# PIC32MZ.net
KiCad netlist of a schematic drawn in Altium Designer
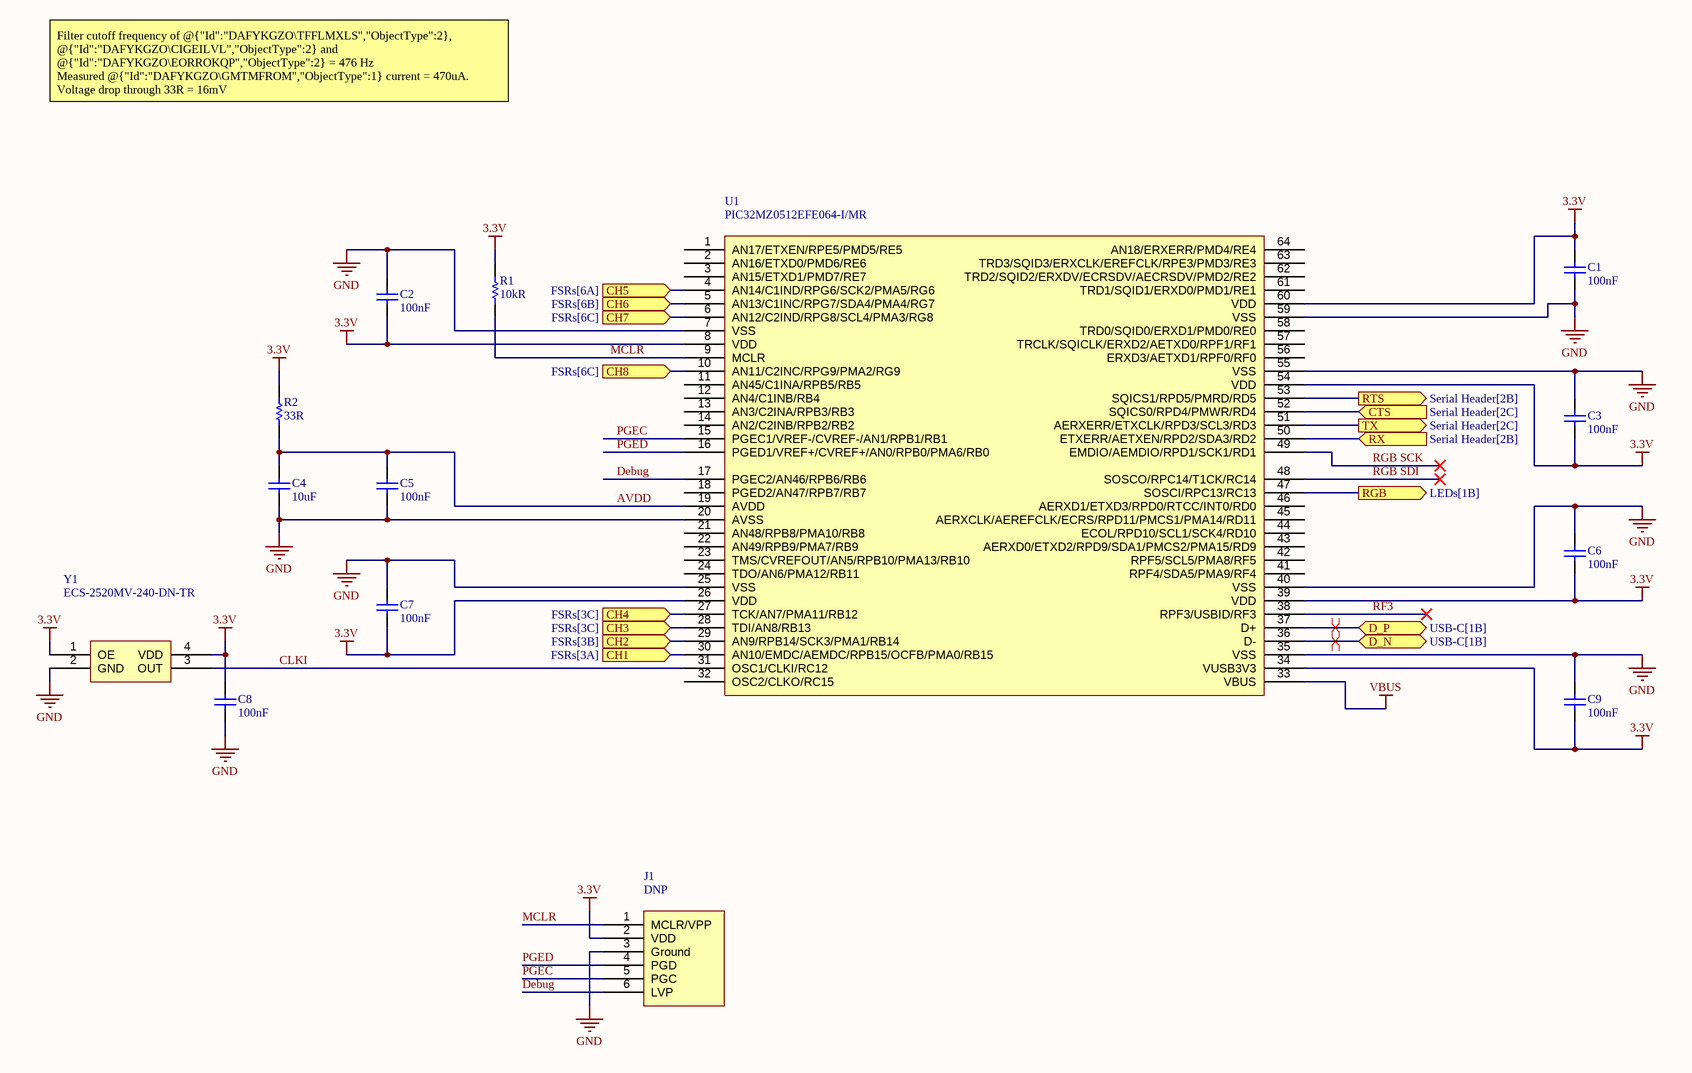
[diagram p0: PIC32MZ.SchDoc]

(export (version "E")
  (design (tool "Eeschema 10.0.6"))
  (components
    (comp (ref "C1") (value "100nF") (footprint "Capacitor 0402") (libsource (lib "x-io") (part "Capacitor")))
    (comp (ref "C2") (value "100nF") (footprint "Capacitor 0402") (libsource (lib "x-io") (part "Capacitor")))
    (comp (ref "C3") (value "100nF") (footprint "Capacitor 0402") (libsource (lib "x-io") (part "Capacitor")))
    (comp (ref "C4") (value "10uF") (footprint "Capacitor 0402") (libsource (lib "x-io") (part "Capacitor")))
    (comp (ref "C5") (value "100nF") (footprint "Capacitor 0402") (libsource (lib "x-io") (part "Capacitor")))
    (comp (ref "C6") (value "100nF") (footprint "Capacitor 0402") (libsource (lib "x-io") (part "Capacitor")))
    (comp (ref "C7") (value "100nF") (footprint "Capacitor 0402") (libsource (lib "x-io") (part "Capacitor")))
    (comp (ref "C8") (value "100nF") (footprint "Capacitor 0402") (libsource (lib "x-io") (part "Capacitor")))
    (comp (ref "C9") (value "100nF") (footprint "Capacitor 0402") (libsource (lib "x-io") (part "Capacitor")))
    (comp (ref "J1")
      (value "DNP")
      (footprint "Tag Connect No Legs")
      (libsource (lib "x-io") (part "MPLAB ICSP"))
    )
    (comp (ref "R1") (value "10kR") (footprint "Resistor 0402") (libsource (lib "x-io") (part "Resistor")))
    (comp (ref "R2") (value "33R") (footprint "Resistor 0402") (libsource (lib "x-io") (part "Resistor")))
    (comp (ref "U1")
      (value "PIC32MZ0512EFE064-I/MR")
      (footprint "QFN-64")
      (libsource (lib "x-io") (part "PIC32MZ2048EFH064"))
    )
    (comp (ref "Y1")
      (value "ECS-2520MV-240-DN-TR")
      (footprint "ECS 2x2.5mm")
      (libsource (lib "x-io") (part "Oscillator"))
    )
  )
  (nets
    (net (code "1") (name "/AVDD") (class "Default")
      (node (ref "C4") (pin "2") (pinfunction "2_2") (pintype "passive"))
      (node (ref "C5") (pin "2") (pinfunction "2_2") (pintype "passive"))
      (node (ref "R2") (pin "1") (pinfunction "1_1") (pintype "passive"))
      (node (ref "U1") (pin "19") (pinfunction "AVDD_19") (pintype "passive"))
    )
    (net (code "2") (name "/CH1") (class "Default")
      (node (ref "U1") (pin "30") (pinfunction "AN10/EMDC/AEMDC/RPB15/OCFB/PMA0/RB15_30") (pintype "passive"))
    )
    (net (code "3") (name "/CH2") (class "Default")
      (node (ref "U1") (pin "29") (pinfunction "AN9/RPB14/SCK3/PMA1/RB14_29") (pintype "passive"))
    )
    (net (code "4") (name "/CH3") (class "Default")
      (node (ref "U1") (pin "28") (pinfunction "TDI/AN8/RB13_28") (pintype "passive"))
    )
    (net (code "5") (name "/CH4") (class "Default")
      (node (ref "U1") (pin "27") (pinfunction "TCK/AN7/PMA11/RB12_27") (pintype "passive"))
    )
    (net (code "6") (name "/CH5") (class "Default")
      (node (ref "U1") (pin "4") (pinfunction "AN14/C1IND/RPG6/SCK2/PMA5/RG6_4") (pintype "passive"))
    )
    (net (code "7") (name "/CH6") (class "Default")
      (node (ref "U1") (pin "5") (pinfunction "AN13/C1INC/RPG7/SDA4/PMA4/RG7_5") (pintype "passive"))
    )
    (net (code "8") (name "/CH7") (class "Default")
      (node (ref "U1") (pin "6") (pinfunction "AN12/C2IND/RPG8/SCL4/PMA3/RG8_6") (pintype "passive"))
    )
    (net (code "9") (name "/CH8") (class "Default")
      (node (ref "U1") (pin "10") (pinfunction "AN11/C2INC/RPG9/PMA2/RG9_10") (pintype "passive"))
    )
    (net (code "10") (name "/CLKI") (class "Default")
      (node (ref "U1") (pin "31") (pinfunction "OSC1/CLKI/RC12_31") (pintype "passive"))
      (node (ref "Y1") (pin "3") (pinfunction "OUT_3") (pintype "passive"))
    )
    (net (code "11") (name "/CTS") (class "Default")
      (node (ref "U1") (pin "52") (pinfunction "SQICS0/RPD4/PMWR/RD4_52") (pintype "passive"))
    )
    (net (code "12") (name "/D_N") (class "Default")
      (node (ref "U1") (pin "36") (pinfunction "D-_36") (pintype "passive"))
    )
    (net (code "13") (name "/D_P") (class "Default")
      (node (ref "U1") (pin "37") (pinfunction "D+_37") (pintype "passive"))
    )
    (net (code "14") (name "/Debug") (class "Default")
      (node (ref "J1") (pin "6") (pinfunction "LVP_6") (pintype "passive"))
      (node (ref "U1") (pin "17") (pinfunction "PGEC2/AN46/RPB6/RB6_17") (pintype "passive"))
    )
    (net (code "15") (name "/MCLR") (class "Default")
      (node (ref "J1") (pin "1") (pinfunction "MCLR/VPP_1") (pintype "passive"))
      (node (ref "R1") (pin "1") (pinfunction "1_1") (pintype "passive"))
      (node (ref "U1") (pin "9") (pinfunction "MCLR_9") (pintype "passive"))
    )
    (net (code "16") (name "/PGEC") (class "Default")
      (node (ref "J1") (pin "5") (pinfunction "PGC_5") (pintype "passive"))
      (node (ref "U1") (pin "15") (pinfunction "PGEC1/VREF-/CVREF-/AN1/RPB1/RB1_15") (pintype "passive"))
    )
    (net (code "17") (name "/PGED") (class "Default")
      (node (ref "J1") (pin "4") (pinfunction "PGD_4") (pintype "passive"))
      (node (ref "U1") (pin "16") (pinfunction "PGED1/VREF+/CVREF+/AN0/RPB0/PMA6/RB0_16") (pintype "passive"))
    )
    (net (code "18") (name "/RF3") (class "Default")
      (node (ref "U1") (pin "38") (pinfunction "RPF3/USBID/RF3_38") (pintype "passive+no_connect"))
    )
    (net (code "19") (name "/RGB") (class "Default")
      (node (ref "U1") (pin "47") (pinfunction "SOSCI/RPC13/RC13_47") (pintype "passive"))
    )
    (net (code "20") (name "/RGB SCK") (class "Default")
      (node (ref "U1") (pin "49") (pinfunction "EMDIO/AEMDIO/RPD1/SCK1/RD1_49") (pintype "passive+no_connect"))
    )
    (net (code "21") (name "/RGB SDI") (class "Default")
      (node (ref "U1") (pin "48") (pinfunction "SOSCO/RPC14/T1CK/RC14_48") (pintype "passive+no_connect"))
    )
    (net (code "22") (name "/RTS") (class "Default")
      (node (ref "U1") (pin "53") (pinfunction "SQICS1/RPD5/PMRD/RD5_53") (pintype "passive"))
    )
    (net (code "23") (name "/RX") (class "Default")
      (node (ref "U1") (pin "50") (pinfunction "ETXERR/AETXEN/RPD2/SDA3/RD2_50") (pintype "passive"))
    )
    (net (code "24") (name "/TX") (class "Default")
      (node (ref "U1") (pin "51") (pinfunction "AERXERR/ETXCLK/RPD3/SCL3/RD3_51") (pintype "passive"))
    )
    (net (code "25") (name "3.3V") (class "Default")
      (node (ref "C1") (pin "2") (pinfunction "2_2") (pintype "passive"))
      (node (ref "C2") (pin "1") (pinfunction "1_1") (pintype "passive"))
      (node (ref "C3") (pin "1") (pinfunction "1_1") (pintype "passive"))
      (node (ref "C6") (pin "1") (pinfunction "1_1") (pintype "passive"))
      (node (ref "C7") (pin "1") (pinfunction "1_1") (pintype "passive"))
      (node (ref "C8") (pin "2") (pinfunction "2_2") (pintype "passive"))
      (node (ref "C9") (pin "1") (pinfunction "1_1") (pintype "passive"))
      (node (ref "J1") (pin "2") (pinfunction "VDD_2") (pintype "passive"))
      (node (ref "R1") (pin "2") (pinfunction "2_2") (pintype "passive"))
      (node (ref "R2") (pin "2") (pinfunction "2_2") (pintype "passive"))
      (node (ref "U1") (pin "26") (pinfunction "VDD_26") (pintype "passive"))
      (node (ref "U1") (pin "34") (pinfunction "VUSB3V3_34") (pintype "passive"))
      (node (ref "U1") (pin "39") (pinfunction "VDD_39") (pintype "passive"))
      (node (ref "U1") (pin "54") (pinfunction "VDD_54") (pintype "passive"))
      (node (ref "U1") (pin "60") (pinfunction "VDD_60") (pintype "passive"))
      (node (ref "U1") (pin "8") (pinfunction "VDD_8") (pintype "passive"))
      (node (ref "Y1") (pin "1") (pinfunction "OE_1") (pintype "passive"))
      (node (ref "Y1") (pin "4") (pinfunction "VDD_4") (pintype "passive"))
    )
    (net (code "26") (name "GND") (class "Default")
      (node (ref "C1") (pin "1") (pinfunction "1_1") (pintype "passive"))
      (node (ref "C2") (pin "2") (pinfunction "2_2") (pintype "passive"))
      (node (ref "C3") (pin "2") (pinfunction "2_2") (pintype "passive"))
      (node (ref "C4") (pin "1") (pinfunction "1_1") (pintype "passive"))
      (node (ref "C5") (pin "1") (pinfunction "1_1") (pintype "passive"))
      (node (ref "C6") (pin "2") (pinfunction "2_2") (pintype "passive"))
      (node (ref "C7") (pin "2") (pinfunction "2_2") (pintype "passive"))
      (node (ref "C8") (pin "1") (pinfunction "1_1") (pintype "passive"))
      (node (ref "C9") (pin "2") (pinfunction "2_2") (pintype "passive"))
      (node (ref "J1") (pin "3") (pinfunction "Ground_3") (pintype "passive"))
      (node (ref "U1") (pin "20") (pinfunction "AVSS_20") (pintype "passive"))
      (node (ref "U1") (pin "25") (pinfunction "VSS_25") (pintype "passive"))
      (node (ref "U1") (pin "35") (pinfunction "VSS_35") (pintype "passive"))
      (node (ref "U1") (pin "40") (pinfunction "VSS_40") (pintype "passive"))
      (node (ref "U1") (pin "55") (pinfunction "VSS_55") (pintype "passive"))
      (node (ref "U1") (pin "59") (pinfunction "VSS_59") (pintype "passive"))
      (node (ref "U1") (pin "7") (pinfunction "VSS_7") (pintype "passive"))
      (node (ref "Y1") (pin "2") (pinfunction "GND_2") (pintype "passive"))
    )
    (net (code "27") (name "VBUS") (class "Default")
      (node (ref "U1") (pin "33") (pinfunction "VBUS_33") (pintype "passive"))
    )
    (net (code "28") (name "unconnected-(U1-AERXCLK{slash}AEREFCLK{slash}ECRS{slash}RPD11{slash}PMCS1{slash}PMA14{slash}RD11-Pad45)") (class "Default")
      (node (ref "U1") (pin "45") (pinfunction "AERXCLK/AEREFCLK/ECRS/RPD11/PMCS1/PMA14/RD11_45") (pintype "passive"))
    )
    (net (code "29") (name "unconnected-(U1-AERXD0{slash}ETXD2{slash}RPD9{slash}SDA1{slash}PMCS2{slash}PMA15{slash}RD9-Pad43)") (class "Default")
      (node (ref "U1") (pin "43") (pinfunction "AERXD0/ETXD2/RPD9/SDA1/PMCS2/PMA15/RD9_43") (pintype "passive"))
    )
    (net (code "30") (name "unconnected-(U1-AERXD1{slash}ETXD3{slash}RPD0{slash}RTCC{slash}INT0{slash}RD0-Pad46)") (class "Default")
      (node (ref "U1") (pin "46") (pinfunction "AERXD1/ETXD3/RPD0/RTCC/INT0/RD0_46") (pintype "passive"))
    )
    (net (code "31") (name "unconnected-(U1-AN2{slash}C2INB{slash}RPB2{slash}RB2-Pad14)") (class "Default")
      (node (ref "U1") (pin "14") (pinfunction "AN2/C2INB/RPB2/RB2_14") (pintype "passive"))
    )
    (net (code "32") (name "unconnected-(U1-AN3{slash}C2INA{slash}RPB3{slash}RB3-Pad13)") (class "Default")
      (node (ref "U1") (pin "13") (pinfunction "AN3/C2INA/RPB3/RB3_13") (pintype "passive"))
    )
    (net (code "33") (name "unconnected-(U1-AN4{slash}C1INB{slash}RB4-Pad12)") (class "Default")
      (node (ref "U1") (pin "12") (pinfunction "AN4/C1INB/RB4_12") (pintype "passive"))
    )
    (net (code "34") (name "unconnected-(U1-AN15{slash}ETXD1{slash}PMD7{slash}RE7-Pad3)") (class "Default")
      (node (ref "U1") (pin "3") (pinfunction "AN15/ETXD1/PMD7/RE7_3") (pintype "passive"))
    )
    (net (code "35") (name "unconnected-(U1-AN16{slash}ETXD0{slash}PMD6{slash}RE6-Pad2)") (class "Default")
      (node (ref "U1") (pin "2") (pinfunction "AN16/ETXD0/PMD6/RE6_2") (pintype "passive"))
    )
    (net (code "36") (name "unconnected-(U1-AN17{slash}ETXEN{slash}RPE5{slash}PMD5{slash}RE5-Pad1)") (class "Default")
      (node (ref "U1") (pin "1") (pinfunction "AN17/ETXEN/RPE5/PMD5/RE5_1") (pintype "passive"))
    )
    (net (code "37") (name "unconnected-(U1-AN18{slash}ERXERR{slash}PMD4{slash}RE4-Pad64)") (class "Default")
      (node (ref "U1") (pin "64") (pinfunction "AN18/ERXERR/PMD4/RE4_64") (pintype "passive"))
    )
    (net (code "38") (name "unconnected-(U1-AN45{slash}C1INA{slash}RPB5{slash}RB5-Pad11)") (class "Default")
      (node (ref "U1") (pin "11") (pinfunction "AN45/C1INA/RPB5/RB5_11") (pintype "passive"))
    )
    (net (code "39") (name "unconnected-(U1-AN48{slash}RPB8{slash}PMA10{slash}RB8-Pad21)") (class "Default")
      (node (ref "U1") (pin "21") (pinfunction "AN48/RPB8/PMA10/RB8_21") (pintype "passive"))
    )
    (net (code "40") (name "unconnected-(U1-AN49{slash}RPB9{slash}PMA7{slash}RB9-Pad22)") (class "Default")
      (node (ref "U1") (pin "22") (pinfunction "AN49/RPB9/PMA7/RB9_22") (pintype "passive"))
    )
    (net (code "41") (name "unconnected-(U1-ECOL{slash}RPD10{slash}SCL1{slash}SCK4{slash}RD10-Pad44)") (class "Default")
      (node (ref "U1") (pin "44") (pinfunction "ECOL/RPD10/SCL1/SCK4/RD10_44") (pintype "passive"))
    )
    (net (code "42") (name "unconnected-(U1-ERXD3{slash}AETXD1{slash}RPF0{slash}RF0-Pad56)") (class "Default")
      (node (ref "U1") (pin "56") (pinfunction "ERXD3/AETXD1/RPF0/RF0_56") (pintype "passive"))
    )
    (net (code "43") (name "unconnected-(U1-OSC2{slash}CLKO{slash}RC15-Pad32)") (class "Default")
      (node (ref "U1") (pin "32") (pinfunction "OSC2/CLKO/RC15_32") (pintype "passive"))
    )
    (net (code "44") (name "unconnected-(U1-PGED2{slash}AN47{slash}RPB7{slash}RB7-Pad18)") (class "Default")
      (node (ref "U1") (pin "18") (pinfunction "PGED2/AN47/RPB7/RB7_18") (pintype "passive"))
    )
    (net (code "45") (name "unconnected-(U1-RPF4{slash}SDA5{slash}PMA9{slash}RF4-Pad41)") (class "Default")
      (node (ref "U1") (pin "41") (pinfunction "RPF4/SDA5/PMA9/RF4_41") (pintype "passive"))
    )
    (net (code "46") (name "unconnected-(U1-RPF5{slash}SCL5{slash}PMA8{slash}RF5-Pad42)") (class "Default")
      (node (ref "U1") (pin "42") (pinfunction "RPF5/SCL5/PMA8/RF5_42") (pintype "passive"))
    )
    (net (code "47") (name "unconnected-(U1-TDO{slash}AN6{slash}PMA12{slash}RB11-Pad24)") (class "Default")
      (node (ref "U1") (pin "24") (pinfunction "TDO/AN6/PMA12/RB11_24") (pintype "passive"))
    )
    (net (code "48") (name "unconnected-(U1-TMS{slash}CVREFOUT{slash}AN5{slash}RPB10{slash}PMA13{slash}RB10-Pad23)") (class "Default")
      (node (ref "U1") (pin "23") (pinfunction "TMS/CVREFOUT/AN5/RPB10/PMA13/RB10_23") (pintype "passive"))
    )
    (net (code "49") (name "unconnected-(U1-TRCLK{slash}SQICLK{slash}ERXD2{slash}AETXD0{slash}RPF1{slash}RF1-Pad57)") (class "Default")
      (node (ref "U1") (pin "57") (pinfunction "TRCLK/SQICLK/ERXD2/AETXD0/RPF1/RF1_57") (pintype "passive"))
    )
    (net (code "50") (name "unconnected-(U1-TRD0{slash}SQID0{slash}ERXD1{slash}PMD0{slash}RE0-Pad58)") (class "Default")
      (node (ref "U1") (pin "58") (pinfunction "TRD0/SQID0/ERXD1/PMD0/RE0_58") (pintype "passive"))
    )
    (net (code "51") (name "unconnected-(U1-TRD1{slash}SQID1{slash}ERXD0{slash}PMD1{slash}RE1-Pad61)") (class "Default")
      (node (ref "U1") (pin "61") (pinfunction "TRD1/SQID1/ERXD0/PMD1/RE1_61") (pintype "passive"))
    )
    (net (code "52") (name "unconnected-(U1-TRD2{slash}SQID2{slash}ERXDV{slash}ECRSDV{slash}AECRSDV{slash}PMD2{slash}RE2-Pad62)") (class "Default")
      (node (ref "U1") (pin "62") (pinfunction "TRD2/SQID2/ERXDV/ECRSDV/AECRSDV/PMD2/RE2_62") (pintype "passive"))
    )
    (net (code "53") (name "unconnected-(U1-TRD3{slash}SQID3{slash}ERXCLK{slash}EREFCLK{slash}RPE3{slash}PMD3{slash}RE3-Pad63)") (class "Default")
      (node (ref "U1") (pin "63") (pinfunction "TRD3/SQID3/ERXCLK/EREFCLK/RPE3/PMD3/RE3_63") (pintype "passive"))
    )
  )
)
